# Busboard_v11.net
KiCad netlist of a schematic drawn in EAGLE
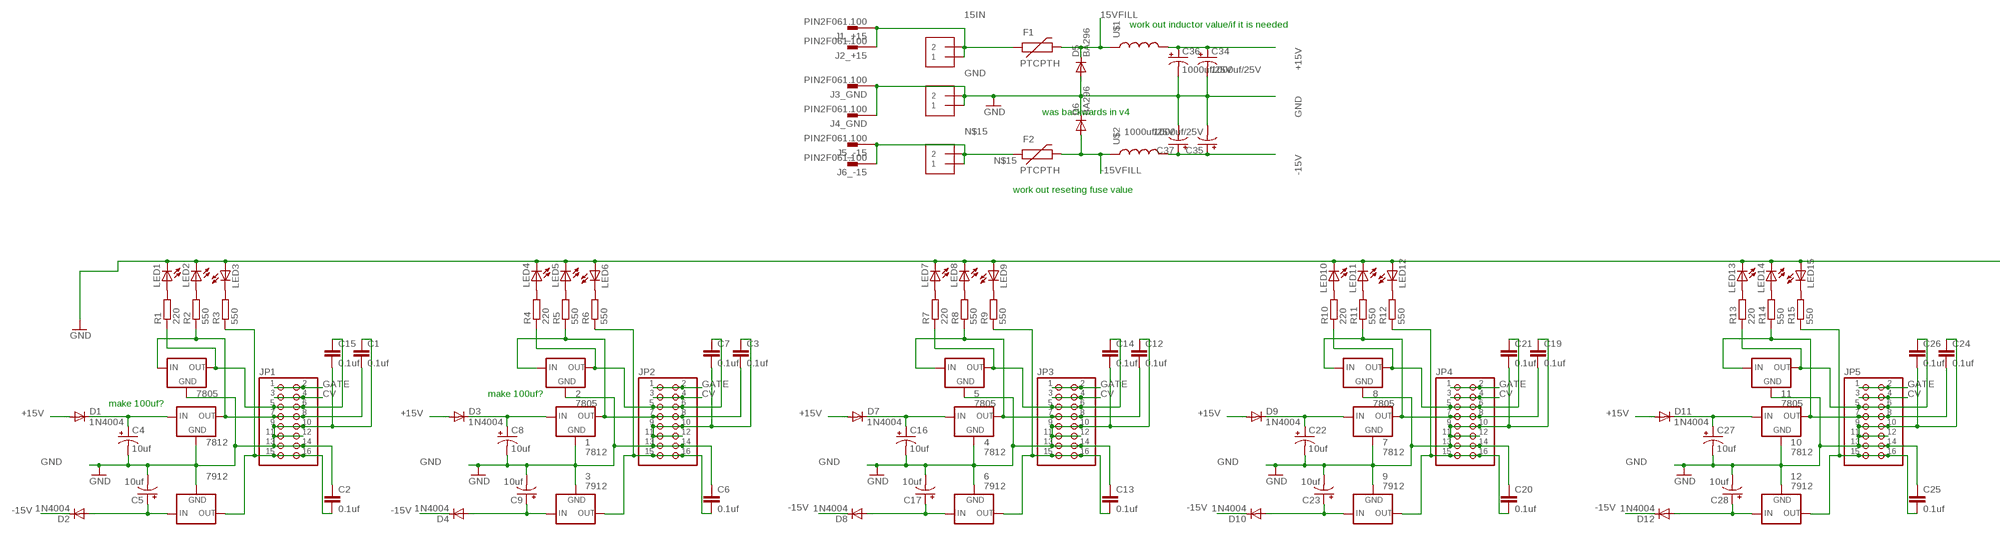
[diagram p0: schematic, sheet 1, part 1 of 2]
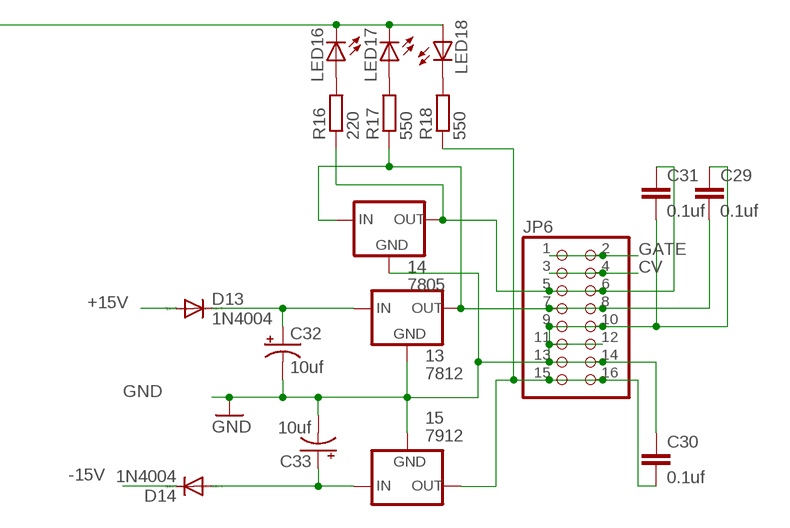
[diagram p1: schematic, sheet 1, part 2 of 2]

(export (version "E")
  (design (tool "Eeschema 10.0.6"))
  (components
    (comp (ref "+15V_DC_IN")
      (value "1X2-3.5MM")
      (footprint "eagle-import:1X2-3.5MM")
      (libsource (lib "eagle-import") (part "1X2-3.5MM"))
    )
    (comp (ref "-15V_DC_IN")
      (value "1X2-3.5MM")
      (footprint "eagle-import:1X2-3.5MM")
      (libsource (lib "eagle-import") (part "1X2-3.5MM"))
    )
    (comp (ref "1")
      (value "7812")
      (footprint "eagle-import:78MXXS")
      (libsource (lib "eagle-import") (part "78MXXS"))
    )
    (comp (ref "2")
      (value "7805")
      (footprint "eagle-import:78MXXS")
      (libsource (lib "eagle-import") (part "78MXXS"))
    )
    (comp (ref "3")
      (value "7912")
      (footprint "eagle-import:79XXS")
      (libsource (lib "eagle-import") (part "79XXS"))
    )
    (comp (ref "4")
      (value "7812")
      (footprint "eagle-import:78MXXS")
      (libsource (lib "eagle-import") (part "78MXXS"))
    )
    (comp (ref "5")
      (value "7805")
      (footprint "eagle-import:78MXXS")
      (libsource (lib "eagle-import") (part "78MXXS"))
    )
    (comp (ref "6")
      (value "7912")
      (footprint "eagle-import:79XXS")
      (libsource (lib "eagle-import") (part "79XXS"))
    )
    (comp (ref "7")
      (value "7812")
      (footprint "eagle-import:78MXXS")
      (libsource (lib "eagle-import") (part "78MXXS"))
    )
    (comp (ref "8")
      (value "7805")
      (footprint "eagle-import:78MXXS")
      (libsource (lib "eagle-import") (part "78MXXS"))
    )
    (comp (ref "9")
      (value "7912")
      (footprint "eagle-import:79XXS")
      (libsource (lib "eagle-import") (part "79XXS"))
    )
    (comp (ref "10")
      (value "7812")
      (footprint "eagle-import:78MXXS")
      (libsource (lib "eagle-import") (part "78MXXS"))
    )
    (comp (ref "11")
      (value "7805")
      (footprint "eagle-import:78MXXS")
      (libsource (lib "eagle-import") (part "78MXXS"))
    )
    (comp (ref "12")
      (value "7912")
      (footprint "eagle-import:79XXS")
      (libsource (lib "eagle-import") (part "79XXS"))
    )
    (comp (ref "13")
      (value "7812")
      (footprint "eagle-import:78MXXS")
      (libsource (lib "eagle-import") (part "78MXXS"))
    )
    (comp (ref "14")
      (value "7805")
      (footprint "eagle-import:78MXXS")
      (libsource (lib "eagle-import") (part "78MXXS"))
    )
    (comp (ref "15")
      (value "7912")
      (footprint "eagle-import:79XXS")
      (libsource (lib "eagle-import") (part "79XXS"))
    )
    (comp (ref "7805")
      (value "78MXXS")
      (footprint "eagle-import:78MXXS")
      (libsource (lib "eagle-import") (part "78MXXS"))
    )
    (comp (ref "7812")
      (value "78MXXS")
      (footprint "eagle-import:78MXXS")
      (libsource (lib "eagle-import") (part "78MXXS"))
    )
    (comp (ref "7912")
      (value "79XXS")
      (footprint "eagle-import:79XXS")
      (libsource (lib "eagle-import") (part "79XXS"))
    )
    (comp (ref "C1")
      (value "0.1uf")
      (footprint "eagle-import:CAP-PTH-SMALL-KIT")
      (libsource (lib "eagle-import") (part "0.1UF-50V-20%(PTH)KIT-EZ"))
    )
    (comp (ref "C2")
      (value "0.1uf")
      (footprint "eagle-import:CAP-PTH-SMALL-KIT")
      (libsource (lib "eagle-import") (part "0.1UF-50V-20%(PTH)KIT-EZ"))
    )
    (comp (ref "C3")
      (value "0.1uf")
      (footprint "eagle-import:CAP-PTH-SMALL-KIT")
      (libsource (lib "eagle-import") (part "0.1UF-50V-20%(PTH)KIT-EZ"))
    )
    (comp (ref "C4")
      (value "10uf")
      (footprint "eagle-import:CPOL-RADIAL-10UF-25V")
      (libsource (lib "eagle-import") (part "10UF-25V-20%(PTH)"))
    )
    (comp (ref "C5")
      (value "10uf")
      (footprint "eagle-import:CPOL-RADIAL-10UF-25V")
      (libsource (lib "eagle-import") (part "10UF-25V-20%(PTH)"))
    )
    (comp (ref "C6")
      (value "0.1uf")
      (footprint "eagle-import:CAP-PTH-SMALL-KIT")
      (libsource (lib "eagle-import") (part "0.1UF-50V-20%(PTH)KIT-EZ"))
    )
    (comp (ref "C7")
      (value "0.1uf")
      (footprint "eagle-import:CAP-PTH-SMALL-KIT")
      (libsource (lib "eagle-import") (part "0.1UF-50V-20%(PTH)KIT-EZ"))
    )
    (comp (ref "C8")
      (value "10uf")
      (footprint "eagle-import:CPOL-RADIAL-10UF-25V")
      (libsource (lib "eagle-import") (part "10UF-25V-20%(PTH)"))
    )
    (comp (ref "C9")
      (value "10uf")
      (footprint "eagle-import:CPOL-RADIAL-10UF-25V")
      (libsource (lib "eagle-import") (part "10UF-25V-20%(PTH)"))
    )
    (comp (ref "C12")
      (value "0.1uf")
      (footprint "eagle-import:CAP-PTH-SMALL-KIT")
      (libsource (lib "eagle-import") (part "0.1UF-50V-20%(PTH)KIT-EZ"))
    )
    (comp (ref "C13")
      (value "0.1uf")
      (footprint "eagle-import:CAP-PTH-SMALL-KIT")
      (libsource (lib "eagle-import") (part "0.1UF-50V-20%(PTH)KIT-EZ"))
    )
    (comp (ref "C14")
      (value "0.1uf")
      (footprint "eagle-import:CAP-PTH-SMALL-KIT")
      (libsource (lib "eagle-import") (part "0.1UF-50V-20%(PTH)KIT-EZ"))
    )
    (comp (ref "C15")
      (value "0.1uf")
      (footprint "eagle-import:CAP-PTH-SMALL-KIT")
      (libsource (lib "eagle-import") (part "0.1UF-50V-20%(PTH)KIT-EZ"))
    )
    (comp (ref "C16")
      (value "10uf")
      (footprint "eagle-import:CPOL-RADIAL-10UF-25V")
      (libsource (lib "eagle-import") (part "10UF-25V-20%(PTH)"))
    )
    (comp (ref "C17")
      (value "10uf")
      (footprint "eagle-import:CPOL-RADIAL-10UF-25V")
      (libsource (lib "eagle-import") (part "10UF-25V-20%(PTH)"))
    )
    (comp (ref "C19")
      (value "0.1uf")
      (footprint "eagle-import:CAP-PTH-SMALL-KIT")
      (libsource (lib "eagle-import") (part "0.1UF-50V-20%(PTH)KIT-EZ"))
    )
    (comp (ref "C20")
      (value "0.1uf")
      (footprint "eagle-import:CAP-PTH-SMALL-KIT")
      (libsource (lib "eagle-import") (part "0.1UF-50V-20%(PTH)KIT-EZ"))
    )
    (comp (ref "C21")
      (value "0.1uf")
      (footprint "eagle-import:CAP-PTH-SMALL-KIT")
      (libsource (lib "eagle-import") (part "0.1UF-50V-20%(PTH)KIT-EZ"))
    )
    (comp (ref "C22")
      (value "10uf")
      (footprint "eagle-import:CPOL-RADIAL-10UF-25V")
      (libsource (lib "eagle-import") (part "10UF-25V-20%(PTH)"))
    )
    (comp (ref "C23")
      (value "10uf")
      (footprint "eagle-import:CPOL-RADIAL-10UF-25V")
      (libsource (lib "eagle-import") (part "10UF-25V-20%(PTH)"))
    )
    (comp (ref "C24")
      (value "0.1uf")
      (footprint "eagle-import:CAP-PTH-SMALL-KIT")
      (libsource (lib "eagle-import") (part "0.1UF-50V-20%(PTH)KIT-EZ"))
    )
    (comp (ref "C25")
      (value "0.1uf")
      (footprint "eagle-import:CAP-PTH-SMALL-KIT")
      (libsource (lib "eagle-import") (part "0.1UF-50V-20%(PTH)KIT-EZ"))
    )
    (comp (ref "C26")
      (value "0.1uf")
      (footprint "eagle-import:CAP-PTH-SMALL-KIT")
      (libsource (lib "eagle-import") (part "0.1UF-50V-20%(PTH)KIT-EZ"))
    )
    (comp (ref "C27")
      (value "10uf")
      (footprint "eagle-import:CPOL-RADIAL-10UF-25V")
      (libsource (lib "eagle-import") (part "10UF-25V-20%(PTH)"))
    )
    (comp (ref "C28")
      (value "10uf")
      (footprint "eagle-import:CPOL-RADIAL-10UF-25V")
      (libsource (lib "eagle-import") (part "10UF-25V-20%(PTH)"))
    )
    (comp (ref "C29")
      (value "0.1uf")
      (footprint "eagle-import:CAP-PTH-SMALL-KIT")
      (libsource (lib "eagle-import") (part "0.1UF-50V-20%(PTH)KIT-EZ"))
    )
    (comp (ref "C30")
      (value "0.1uf")
      (footprint "eagle-import:CAP-PTH-SMALL-KIT")
      (libsource (lib "eagle-import") (part "0.1UF-50V-20%(PTH)KIT-EZ"))
    )
    (comp (ref "C31")
      (value "0.1uf")
      (footprint "eagle-import:CAP-PTH-SMALL-KIT")
      (libsource (lib "eagle-import") (part "0.1UF-50V-20%(PTH)KIT-EZ"))
    )
    (comp (ref "C32")
      (value "10uf")
      (footprint "eagle-import:CPOL-RADIAL-10UF-25V")
      (libsource (lib "eagle-import") (part "10UF-25V-20%(PTH)"))
    )
    (comp (ref "C33")
      (value "10uf")
      (footprint "eagle-import:CPOL-RADIAL-10UF-25V")
      (libsource (lib "eagle-import") (part "10UF-25V-20%(PTH)"))
    )
    (comp (ref "C34")
      (value "1000uf/25V")
      (footprint "eagle-import:CPOL-RADIAL-1000UF-25V-KIT")
      (libsource (lib "eagle-import") (part "1000UF-25V(PTH)KIT"))
    )
    (comp (ref "C35")
      (value "1000uf/25V")
      (footprint "eagle-import:CPOL-RADIAL-1000UF-25V-KIT")
      (libsource (lib "eagle-import") (part "1000UF-25V(PTH)KIT"))
    )
    (comp (ref "C36")
      (value "1000uf/25V")
      (footprint "eagle-import:CPOL-RADIAL-1000UF-25V-KIT")
      (libsource (lib "eagle-import") (part "1000UF-25V(PTH)KIT"))
    )
    (comp (ref "C37")
      (value "1000uf/25V")
      (footprint "eagle-import:CPOL-RADIAL-1000UF-25V-KIT")
      (libsource (lib "eagle-import") (part "1000UF-25V(PTH)KIT"))
    )
    (comp (ref "D1")
      (value "1N4004")
      (footprint "eagle-import:DO41-10")
      (libsource (lib "eagle-import") (part "1N4004"))
    )
    (comp (ref "D2")
      (value "1N4004")
      (footprint "eagle-import:DO41-10")
      (libsource (lib "eagle-import") (part "1N4004"))
    )
    (comp (ref "D3")
      (value "1N4004")
      (footprint "eagle-import:DO41-10")
      (libsource (lib "eagle-import") (part "1N4004"))
    )
    (comp (ref "D4")
      (value "1N4004")
      (footprint "eagle-import:DO41-10")
      (libsource (lib "eagle-import") (part "1N4004"))
    )
    (comp (ref "D5")
      (value "BA296")
      (footprint "eagle-import:P2-15")
      (libsource (lib "eagle-import") (part "BA296"))
    )
    (comp (ref "D6")
      (value "BA296")
      (footprint "eagle-import:P2-15")
      (libsource (lib "eagle-import") (part "BA296"))
    )
    (comp (ref "D7")
      (value "1N4004")
      (footprint "eagle-import:DO41-10")
      (libsource (lib "eagle-import") (part "1N4004"))
    )
    (comp (ref "D8")
      (value "1N4004")
      (footprint "eagle-import:DO41-10")
      (libsource (lib "eagle-import") (part "1N4004"))
    )
    (comp (ref "D9")
      (value "1N4004")
      (footprint "eagle-import:DO41-10")
      (libsource (lib "eagle-import") (part "1N4004"))
    )
    (comp (ref "D10")
      (value "1N4004")
      (footprint "eagle-import:DO41-10")
      (libsource (lib "eagle-import") (part "1N4004"))
    )
    (comp (ref "D11")
      (value "1N4004")
      (footprint "eagle-import:DO41-10")
      (libsource (lib "eagle-import") (part "1N4004"))
    )
    (comp (ref "D12")
      (value "1N4004")
      (footprint "eagle-import:DO41-10")
      (libsource (lib "eagle-import") (part "1N4004"))
    )
    (comp (ref "D13")
      (value "1N4004")
      (footprint "eagle-import:DO41-10")
      (libsource (lib "eagle-import") (part "1N4004"))
    )
    (comp (ref "D14")
      (value "1N4004")
      (footprint "eagle-import:DO41-10")
      (libsource (lib "eagle-import") (part "1N4004"))
    )
    (comp (ref "F1")
      (value "PTCPTH")
      (footprint "eagle-import:PTC")
      (libsource (lib "eagle-import") (part "PTCPTH"))
    )
    (comp (ref "F2")
      (value "PTCPTH")
      (footprint "eagle-import:PTC")
      (libsource (lib "eagle-import") (part "PTCPTH"))
    )
    (comp (ref "GND_IN")
      (value "1X2-3.5MM")
      (footprint "eagle-import:1X2-3.5MM")
      (libsource (lib "eagle-import") (part "1X2-3.5MM"))
    )
    (comp (ref "J1_+15")
      (value "PIN2F061.100")
      (footprint "eagle-import:F061.100")
      (libsource (lib "eagle-import") (part "PIN2F061.100"))
    )
    (comp (ref "J2_+15")
      (value "PIN2F061.100")
      (footprint "eagle-import:F061.100")
      (libsource (lib "eagle-import") (part "PIN2F061.100"))
    )
    (comp (ref "J3_GND")
      (value "PIN2F061.100")
      (footprint "eagle-import:F061.100")
      (libsource (lib "eagle-import") (part "PIN2F061.100"))
    )
    (comp (ref "J4_GND")
      (value "PIN2F061.100")
      (footprint "eagle-import:F061.100")
      (libsource (lib "eagle-import") (part "PIN2F061.100"))
    )
    (comp (ref "J5_-15")
      (value "PIN2F061.100")
      (footprint "eagle-import:F061.100")
      (libsource (lib "eagle-import") (part "PIN2F061.100"))
    )
    (comp (ref "J6_-15")
      (value "PIN2F061.100")
      (footprint "eagle-import:F061.100")
      (libsource (lib "eagle-import") (part "PIN2F061.100"))
    )
    (comp (ref "JP1")
      (value "PINHD-2X8")
      (footprint "eagle-import:2X08")
      (libsource (lib "eagle-import") (part "PINHD-2X8"))
    )
    (comp (ref "JP2")
      (value "PINHD-2X8")
      (footprint "eagle-import:2X08")
      (libsource (lib "eagle-import") (part "PINHD-2X8"))
    )
    (comp (ref "JP3")
      (value "PINHD-2X8")
      (footprint "eagle-import:2X08")
      (libsource (lib "eagle-import") (part "PINHD-2X8"))
    )
    (comp (ref "JP4")
      (value "PINHD-2X8")
      (footprint "eagle-import:2X08")
      (libsource (lib "eagle-import") (part "PINHD-2X8"))
    )
    (comp (ref "JP5")
      (value "PINHD-2X8")
      (footprint "eagle-import:2X08")
      (libsource (lib "eagle-import") (part "PINHD-2X8"))
    )
    (comp (ref "JP6")
      (value "PINHD-2X8")
      (footprint "eagle-import:2X08")
      (libsource (lib "eagle-import") (part "PINHD-2X8"))
    )
    (comp (ref "LED1")
      (value "LED3MM")
      (footprint "eagle-import:LED3MM")
      (libsource (lib "eagle-import") (part "LED3MM"))
    )
    (comp (ref "LED2")
      (value "LED3MM")
      (footprint "eagle-import:LED3MM")
      (libsource (lib "eagle-import") (part "LED3MM"))
    )
    (comp (ref "LED3")
      (value "LED3MM")
      (footprint "eagle-import:LED3MM")
      (libsource (lib "eagle-import") (part "LED3MM"))
    )
    (comp (ref "LED4")
      (value "LED3MM")
      (footprint "eagle-import:LED3MM")
      (libsource (lib "eagle-import") (part "LED3MM"))
    )
    (comp (ref "LED5")
      (value "LED3MM")
      (footprint "eagle-import:LED3MM")
      (libsource (lib "eagle-import") (part "LED3MM"))
    )
    (comp (ref "LED6")
      (value "LED3MM")
      (footprint "eagle-import:LED3MM")
      (libsource (lib "eagle-import") (part "LED3MM"))
    )
    (comp (ref "LED7")
      (value "LED3MM")
      (footprint "eagle-import:LED3MM")
      (libsource (lib "eagle-import") (part "LED3MM"))
    )
    (comp (ref "LED8")
      (value "LED3MM")
      (footprint "eagle-import:LED3MM")
      (libsource (lib "eagle-import") (part "LED3MM"))
    )
    (comp (ref "LED9")
      (value "LED3MM")
      (footprint "eagle-import:LED3MM")
      (libsource (lib "eagle-import") (part "LED3MM"))
    )
    (comp (ref "LED10")
      (value "LED3MM")
      (footprint "eagle-import:LED3MM")
      (libsource (lib "eagle-import") (part "LED3MM"))
    )
    (comp (ref "LED11")
      (value "LED3MM")
      (footprint "eagle-import:LED3MM")
      (libsource (lib "eagle-import") (part "LED3MM"))
    )
    (comp (ref "LED12")
      (value "LED3MM")
      (footprint "eagle-import:LED3MM")
      (libsource (lib "eagle-import") (part "LED3MM"))
    )
    (comp (ref "LED13")
      (value "LED3MM")
      (footprint "eagle-import:LED3MM")
      (libsource (lib "eagle-import") (part "LED3MM"))
    )
    (comp (ref "LED14")
      (value "LED3MM")
      (footprint "eagle-import:LED3MM")
      (libsource (lib "eagle-import") (part "LED3MM"))
    )
    (comp (ref "LED15")
      (value "LED3MM")
      (footprint "eagle-import:LED3MM")
      (libsource (lib "eagle-import") (part "LED3MM"))
    )
    (comp (ref "LED16")
      (value "LED3MM")
      (footprint "eagle-import:LED3MM")
      (libsource (lib "eagle-import") (part "LED3MM"))
    )
    (comp (ref "LED17")
      (value "LED3MM")
      (footprint "eagle-import:LED3MM")
      (libsource (lib "eagle-import") (part "LED3MM"))
    )
    (comp (ref "LED18")
      (value "LED3MM")
      (footprint "eagle-import:LED3MM")
      (libsource (lib "eagle-import") (part "LED3MM"))
    )
    (comp (ref "R1")
      (value "220")
      (footprint "eagle-import:0207_5V")
      (libsource (lib "eagle-import") (part "R-EU_0207/5V"))
    )
    (comp (ref "R2")
      (value "550")
      (footprint "eagle-import:0207_5V")
      (libsource (lib "eagle-import") (part "R-EU_0207/5V"))
    )
    (comp (ref "R3")
      (value "550")
      (footprint "eagle-import:0207_5V")
      (libsource (lib "eagle-import") (part "R-EU_0207/5V"))
    )
    (comp (ref "R4")
      (value "220")
      (footprint "eagle-import:0207_5V")
      (libsource (lib "eagle-import") (part "R-EU_0207/5V"))
    )
    (comp (ref "R5")
      (value "550")
      (footprint "eagle-import:0207_5V")
      (libsource (lib "eagle-import") (part "R-EU_0207/5V"))
    )
    (comp (ref "R6")
      (value "550")
      (footprint "eagle-import:0207_5V")
      (libsource (lib "eagle-import") (part "R-EU_0207/5V"))
    )
    (comp (ref "R7")
      (value "220")
      (footprint "eagle-import:0207_5V")
      (libsource (lib "eagle-import") (part "R-EU_0207/5V"))
    )
    (comp (ref "R8")
      (value "550")
      (footprint "eagle-import:0207_5V")
      (libsource (lib "eagle-import") (part "R-EU_0207/5V"))
    )
    (comp (ref "R9")
      (value "550")
      (footprint "eagle-import:0207_5V")
      (libsource (lib "eagle-import") (part "R-EU_0207/5V"))
    )
    (comp (ref "R10")
      (value "220")
      (footprint "eagle-import:0207_5V")
      (libsource (lib "eagle-import") (part "R-EU_0207/5V"))
    )
    (comp (ref "R11")
      (value "550")
      (footprint "eagle-import:0207_5V")
      (libsource (lib "eagle-import") (part "R-EU_0207/5V"))
    )
    (comp (ref "R12")
      (value "550")
      (footprint "eagle-import:0207_5V")
      (libsource (lib "eagle-import") (part "R-EU_0207/5V"))
    )
    (comp (ref "R13")
      (value "220")
      (footprint "eagle-import:0207_5V")
      (libsource (lib "eagle-import") (part "R-EU_0207/5V"))
    )
    (comp (ref "R14")
      (value "550")
      (footprint "eagle-import:0207_5V")
      (libsource (lib "eagle-import") (part "R-EU_0207/5V"))
    )
    (comp (ref "R15")
      (value "550")
      (footprint "eagle-import:0207_5V")
      (libsource (lib "eagle-import") (part "R-EU_0207/5V"))
    )
    (comp (ref "R16")
      (value "220")
      (footprint "eagle-import:0207_5V")
      (libsource (lib "eagle-import") (part "R-EU_0207/5V"))
    )
    (comp (ref "R17")
      (value "550")
      (footprint "eagle-import:0207_5V")
      (libsource (lib "eagle-import") (part "R-EU_0207/5V"))
    )
    (comp (ref "R18")
      (value "550")
      (footprint "eagle-import:0207_5V")
      (libsource (lib "eagle-import") (part "R-EU_0207/5V"))
    )
    (comp (ref "U$1")
      (value "INDUCTORRLB0912")
      (footprint "eagle-import:RLB0912")
      (libsource (lib "eagle-import") (part "INDUCTORRLB0912"))
    )
    (comp (ref "U$2")
      (value "INDUCTORRLB0912")
      (footprint "eagle-import:RLB0912")
      (libsource (lib "eagle-import") (part "INDUCTORRLB0912"))
    )
  )
  (nets
    (net (code "1") (name "/+15V") (class "Default")
      (node (ref "C34") (pin "+") (pinfunction "+_+") (pintype "passive"))
      (node (ref "C36") (pin "+") (pinfunction "+_+") (pintype "passive"))
      (node (ref "D1") (pin "A") (pinfunction "A_A") (pintype "passive"))
      (node (ref "D11") (pin "A") (pinfunction "A_A") (pintype "passive"))
      (node (ref "D13") (pin "A") (pinfunction "A_A") (pintype "passive"))
      (node (ref "D3") (pin "A") (pinfunction "A_A") (pintype "passive"))
      (node (ref "D7") (pin "A") (pinfunction "A_A") (pintype "passive"))
      (node (ref "D9") (pin "A") (pinfunction "A_A") (pintype "passive"))
      (node (ref "U$1") (pin "2") (pinfunction "2_2") (pintype "passive"))
    )
    (net (code "2") (name "/-15V") (class "Default")
      (node (ref "C35") (pin "+") (pinfunction "+_+") (pintype "passive"))
      (node (ref "C37") (pin "+") (pinfunction "+_+") (pintype "passive"))
      (node (ref "D10") (pin "C") (pinfunction "C_C") (pintype "passive"))
      (node (ref "D12") (pin "C") (pinfunction "C_C") (pintype "passive"))
      (node (ref "D14") (pin "C") (pinfunction "C_C") (pintype "passive"))
      (node (ref "D2") (pin "C") (pinfunction "C_C") (pintype "passive"))
      (node (ref "D4") (pin "C") (pinfunction "C_C") (pintype "passive"))
      (node (ref "D8") (pin "C") (pinfunction "C_C") (pintype "passive"))
      (node (ref "U$2") (pin "2") (pinfunction "2_2") (pintype "passive"))
    )
    (net (code "3") (name "/-15VFILL") (class "Default")
      (node (ref "D6") (pin "A") (pinfunction "A_A") (pintype "passive"))
      (node (ref "F2") (pin "P$2") (pinfunction "2_P$2") (pintype "bidirectional"))
      (node (ref "U$2") (pin "1") (pinfunction "1_1") (pintype "passive"))
    )
    (net (code "4") (name "/15IN") (class "Default")
      (node (ref "+15V_DC_IN") (pin "1") (pinfunction "1_1") (pintype "passive"))
      (node (ref "+15V_DC_IN") (pin "2") (pinfunction "2_2") (pintype "passive"))
      (node (ref "F1") (pin "P$1") (pinfunction "1_P$1") (pintype "bidirectional"))
      (node (ref "J1_+15") (pin "A1") (pinfunction "1_A1") (pintype "passive"))
      (node (ref "J1_+15") (pin "A2") (pinfunction "1_A2") (pintype "passive"))
      (node (ref "J2_+15") (pin "A1") (pinfunction "1_A1") (pintype "passive"))
      (node (ref "J2_+15") (pin "A2") (pinfunction "1_A2") (pintype "passive"))
    )
    (net (code "5") (name "/15VFILL") (class "Default")
      (node (ref "D5") (pin "C") (pinfunction "C_C") (pintype "passive"))
      (node (ref "F1") (pin "P$2") (pinfunction "2_P$2") (pintype "bidirectional"))
      (node (ref "U$1") (pin "1") (pinfunction "1_1") (pintype "passive"))
    )
    (net (code "6") (name "/CV") (class "Default")
      (node (ref "JP1") (pin "3") (pinfunction "3_3") (pintype "passive"))
      (node (ref "JP1") (pin "4") (pinfunction "4_4") (pintype "passive"))
      (node (ref "JP2") (pin "3") (pinfunction "3_3") (pintype "passive"))
      (node (ref "JP2") (pin "4") (pinfunction "4_4") (pintype "passive"))
      (node (ref "JP3") (pin "3") (pinfunction "3_3") (pintype "passive"))
      (node (ref "JP3") (pin "4") (pinfunction "4_4") (pintype "passive"))
      (node (ref "JP4") (pin "3") (pinfunction "3_3") (pintype "passive"))
      (node (ref "JP4") (pin "4") (pinfunction "4_4") (pintype "passive"))
      (node (ref "JP5") (pin "3") (pinfunction "3_3") (pintype "passive"))
      (node (ref "JP5") (pin "4") (pinfunction "4_4") (pintype "passive"))
      (node (ref "JP6") (pin "3") (pinfunction "3_3") (pintype "passive"))
      (node (ref "JP6") (pin "4") (pinfunction "4_4") (pintype "passive"))
    )
    (net (code "7") (name "/GATE") (class "Default")
      (node (ref "JP1") (pin "1") (pinfunction "1_1") (pintype "passive"))
      (node (ref "JP1") (pin "2") (pinfunction "2_2") (pintype "passive"))
      (node (ref "JP2") (pin "1") (pinfunction "1_1") (pintype "passive"))
      (node (ref "JP2") (pin "2") (pinfunction "2_2") (pintype "passive"))
      (node (ref "JP3") (pin "1") (pinfunction "1_1") (pintype "passive"))
      (node (ref "JP3") (pin "2") (pinfunction "2_2") (pintype "passive"))
      (node (ref "JP4") (pin "1") (pinfunction "1_1") (pintype "passive"))
      (node (ref "JP4") (pin "2") (pinfunction "2_2") (pintype "passive"))
      (node (ref "JP5") (pin "1") (pinfunction "1_1") (pintype "passive"))
      (node (ref "JP5") (pin "2") (pinfunction "2_2") (pintype "passive"))
      (node (ref "JP6") (pin "1") (pinfunction "1_1") (pintype "passive"))
      (node (ref "JP6") (pin "2") (pinfunction "2_2") (pintype "passive"))
    )
    (net (code "8") (name "/N$15") (class "Default")
      (node (ref "-15V_DC_IN") (pin "1") (pinfunction "1_1") (pintype "passive"))
      (node (ref "-15V_DC_IN") (pin "2") (pinfunction "2_2") (pintype "passive"))
      (node (ref "F2") (pin "P$1") (pinfunction "1_P$1") (pintype "bidirectional"))
      (node (ref "J5_-15") (pin "A1") (pinfunction "1_A1") (pintype "passive"))
      (node (ref "J5_-15") (pin "A2") (pinfunction "1_A2") (pintype "passive"))
      (node (ref "J6_-15") (pin "A1") (pinfunction "1_A1") (pintype "passive"))
      (node (ref "J6_-15") (pin "A2") (pinfunction "1_A2") (pintype "passive"))
    )
    (net (code "9") (name "GND") (class "Default")
      (node (ref "1") (pin "GND") (pinfunction "GND_GND") (pintype "input"))
      (node (ref "10") (pin "GND") (pinfunction "GND_GND") (pintype "input"))
      (node (ref "11") (pin "GND") (pinfunction "GND_GND") (pintype "input"))
      (node (ref "12") (pin "GND") (pinfunction "GND_GND") (pintype "input"))
      (node (ref "13") (pin "GND") (pinfunction "GND_GND") (pintype "input"))
      (node (ref "14") (pin "GND") (pinfunction "GND_GND") (pintype "input"))
      (node (ref "15") (pin "GND") (pinfunction "GND_GND") (pintype "input"))
      (node (ref "2") (pin "GND") (pinfunction "GND_GND") (pintype "input"))
      (node (ref "3") (pin "GND") (pinfunction "GND_GND") (pintype "input"))
      (node (ref "4") (pin "GND") (pinfunction "GND_GND") (pintype "input"))
      (node (ref "5") (pin "GND") (pinfunction "GND_GND") (pintype "input"))
      (node (ref "6") (pin "GND") (pinfunction "GND_GND") (pintype "input"))
      (node (ref "7") (pin "GND") (pinfunction "GND_GND") (pintype "input"))
      (node (ref "7805") (pin "GND") (pinfunction "GND_GND") (pintype "input"))
      (node (ref "7812") (pin "GND") (pinfunction "GND_GND") (pintype "input"))
      (node (ref "7912") (pin "GND") (pinfunction "GND_GND") (pintype "input"))
      (node (ref "8") (pin "GND") (pinfunction "GND_GND") (pintype "input"))
      (node (ref "9") (pin "GND") (pinfunction "GND_GND") (pintype "input"))
      (node (ref "C1") (pin "1") (pinfunction "1_1") (pintype "passive"))
      (node (ref "C12") (pin "1") (pinfunction "1_1") (pintype "passive"))
      (node (ref "C13") (pin "1") (pinfunction "1_1") (pintype "passive"))
      (node (ref "C14") (pin "2") (pinfunction "2_2") (pintype "passive"))
      (node (ref "C15") (pin "2") (pinfunction "2_2") (pintype "passive"))
      (node (ref "C16") (pin "2") (pinfunction "-_2") (pintype "passive"))
      (node (ref "C17") (pin "2") (pinfunction "-_2") (pintype "passive"))
      (node (ref "C19") (pin "1") (pinfunction "1_1") (pintype "passive"))
      (node (ref "C2") (pin "1") (pinfunction "1_1") (pintype "passive"))
      (node (ref "C20") (pin "1") (pinfunction "1_1") (pintype "passive"))
      (node (ref "C21") (pin "2") (pinfunction "2_2") (pintype "passive"))
      (node (ref "C22") (pin "2") (pinfunction "-_2") (pintype "passive"))
      (node (ref "C23") (pin "2") (pinfunction "-_2") (pintype "passive"))
      (node (ref "C24") (pin "1") (pinfunction "1_1") (pintype "passive"))
      (node (ref "C25") (pin "1") (pinfunction "1_1") (pintype "passive"))
      (node (ref "C26") (pin "2") (pinfunction "2_2") (pintype "passive"))
      (node (ref "C27") (pin "2") (pinfunction "-_2") (pintype "passive"))
      (node (ref "C28") (pin "2") (pinfunction "-_2") (pintype "passive"))
      (node (ref "C29") (pin "1") (pinfunction "1_1") (pintype "passive"))
      (node (ref "C3") (pin "1") (pinfunction "1_1") (pintype "passive"))
      (node (ref "C30") (pin "1") (pinfunction "1_1") (pintype "passive"))
      (node (ref "C31") (pin "2") (pinfunction "2_2") (pintype "passive"))
      (node (ref "C32") (pin "2") (pinfunction "-_2") (pintype "passive"))
      (node (ref "C33") (pin "2") (pinfunction "-_2") (pintype "passive"))
      (node (ref "C34") (pin "-") (pinfunction "-_-") (pintype "passive"))
      (node (ref "C35") (pin "-") (pinfunction "-_-") (pintype "passive"))
      (node (ref "C36") (pin "-") (pinfunction "-_-") (pintype "passive"))
      (node (ref "C37") (pin "-") (pinfunction "-_-") (pintype "passive"))
      (node (ref "C4") (pin "2") (pinfunction "-_2") (pintype "passive"))
      (node (ref "C5") (pin "2") (pinfunction "-_2") (pintype "passive"))
      (node (ref "C6") (pin "1") (pinfunction "1_1") (pintype "passive"))
      (node (ref "C7") (pin "2") (pinfunction "2_2") (pintype "passive"))
      (node (ref "C8") (pin "2") (pinfunction "-_2") (pintype "passive"))
      (node (ref "C9") (pin "2") (pinfunction "-_2") (pintype "passive"))
      (node (ref "D5") (pin "A") (pinfunction "A_A") (pintype "passive"))
      (node (ref "D6") (pin "C") (pinfunction "C_C") (pintype "passive"))
      (node (ref "GND_IN") (pin "1") (pinfunction "1_1") (pintype "passive"))
      (node (ref "GND_IN") (pin "2") (pinfunction "2_2") (pintype "passive"))
      (node (ref "J3_GND") (pin "A1") (pinfunction "1_A1") (pintype "passive"))
      (node (ref "J3_GND") (pin "A2") (pinfunction "1_A2") (pintype "passive"))
      (node (ref "J4_GND") (pin "A1") (pinfunction "1_A1") (pintype "passive"))
      (node (ref "J4_GND") (pin "A2") (pinfunction "1_A2") (pintype "passive"))
      (node (ref "JP1") (pin "10") (pinfunction "10_10") (pintype "passive"))
      (node (ref "JP1") (pin "11") (pinfunction "11_11") (pintype "passive"))
      (node (ref "JP1") (pin "12") (pinfunction "12_12") (pintype "passive"))
      (node (ref "JP1") (pin "13") (pinfunction "13_13") (pintype "passive"))
      (node (ref "JP1") (pin "14") (pinfunction "14_14") (pintype "passive"))
      (node (ref "JP1") (pin "9") (pinfunction "9_9") (pintype "passive"))
      (node (ref "JP2") (pin "10") (pinfunction "10_10") (pintype "passive"))
      (node (ref "JP2") (pin "11") (pinfunction "11_11") (pintype "passive"))
      (node (ref "JP2") (pin "12") (pinfunction "12_12") (pintype "passive"))
      (node (ref "JP2") (pin "13") (pinfunction "13_13") (pintype "passive"))
      (node (ref "JP2") (pin "14") (pinfunction "14_14") (pintype "passive"))
      (node (ref "JP2") (pin "9") (pinfunction "9_9") (pintype "passive"))
      (node (ref "JP3") (pin "10") (pinfunction "10_10") (pintype "passive"))
      (node (ref "JP3") (pin "11") (pinfunction "11_11") (pintype "passive"))
      (node (ref "JP3") (pin "12") (pinfunction "12_12") (pintype "passive"))
      (node (ref "JP3") (pin "13") (pinfunction "13_13") (pintype "passive"))
      (node (ref "JP3") (pin "14") (pinfunction "14_14") (pintype "passive"))
      (node (ref "JP3") (pin "9") (pinfunction "9_9") (pintype "passive"))
      (node (ref "JP4") (pin "10") (pinfunction "10_10") (pintype "passive"))
      (node (ref "JP4") (pin "11") (pinfunction "11_11") (pintype "passive"))
      (node (ref "JP4") (pin "12") (pinfunction "12_12") (pintype "passive"))
      (node (ref "JP4") (pin "13") (pinfunction "13_13") (pintype "passive"))
      (node (ref "JP4") (pin "14") (pinfunction "14_14") (pintype "passive"))
      (node (ref "JP4") (pin "9") (pinfunction "9_9") (pintype "passive"))
      (node (ref "JP5") (pin "10") (pinfunction "10_10") (pintype "passive"))
      (node (ref "JP5") (pin "11") (pinfunction "11_11") (pintype "passive"))
      (node (ref "JP5") (pin "12") (pinfunction "12_12") (pintype "passive"))
      (node (ref "JP5") (pin "13") (pinfunction "13_13") (pintype "passive"))
      (node (ref "JP5") (pin "14") (pinfunction "14_14") (pintype "passive"))
      (node (ref "JP5") (pin "9") (pinfunction "9_9") (pintype "passive"))
      (node (ref "JP6") (pin "10") (pinfunction "10_10") (pintype "passive"))
      (node (ref "JP6") (pin "11") (pinfunction "11_11") (pintype "passive"))
      (node (ref "JP6") (pin "12") (pinfunction "12_12") (pintype "passive"))
      (node (ref "JP6") (pin "13") (pinfunction "13_13") (pintype "passive"))
      (node (ref "JP6") (pin "14") (pinfunction "14_14") (pintype "passive"))
      (node (ref "JP6") (pin "9") (pinfunction "9_9") (pintype "passive"))
      (node (ref "LED1") (pin "K") (pinfunction "C_K") (pintype "passive"))
      (node (ref "LED10") (pin "K") (pinfunction "C_K") (pintype "passive"))
      (node (ref "LED11") (pin "K") (pinfunction "C_K") (pintype "passive"))
      (node (ref "LED12") (pin "A") (pinfunction "A_A") (pintype "passive"))
      (node (ref "LED13") (pin "K") (pinfunction "C_K") (pintype "passive"))
      (node (ref "LED14") (pin "K") (pinfunction "C_K") (pintype "passive"))
      (node (ref "LED15") (pin "A") (pinfunction "A_A") (pintype "passive"))
      (node (ref "LED16") (pin "K") (pinfunction "C_K") (pintype "passive"))
      (node (ref "LED17") (pin "K") (pinfunction "C_K") (pintype "passive"))
      (node (ref "LED18") (pin "A") (pinfunction "A_A") (pintype "passive"))
      (node (ref "LED2") (pin "K") (pinfunction "C_K") (pintype "passive"))
      (node (ref "LED3") (pin "A") (pinfunction "A_A") (pintype "passive"))
      (node (ref "LED4") (pin "K") (pinfunction "C_K") (pintype "passive"))
      (node (ref "LED5") (pin "K") (pinfunction "C_K") (pintype "passive"))
      (node (ref "LED6") (pin "A") (pinfunction "A_A") (pintype "passive"))
      (node (ref "LED7") (pin "K") (pinfunction "C_K") (pintype "passive"))
      (node (ref "LED8") (pin "K") (pinfunction "C_K") (pintype "passive"))
      (node (ref "LED9") (pin "A") (pinfunction "A_A") (pintype "passive"))
    )
    (net (code "10") (name "Net-(1-PadOUT)") (class "Default")
      (node (ref "1") (pin "OUT") (pinfunction "OUT_OUT") (pintype "passive"))
      (node (ref "2") (pin "IN") (pinfunction "IN_IN") (pintype "input"))
      (node (ref "C3") (pin "2") (pinfunction "2_2") (pintype "passive"))
      (node (ref "JP2") (pin "7") (pinfunction "7_7") (pintype "passive"))
      (node (ref "JP2") (pin "8") (pinfunction "8_8") (pintype "passive"))
      (node (ref "R5") (pin "1") (pinfunction "1_1") (pintype "passive"))
    )
    (net (code "11") (name "Net-(2-PadOUT)") (class "Default")
      (node (ref "2") (pin "OUT") (pinfunction "OUT_OUT") (pintype "passive"))
      (node (ref "C7") (pin "1") (pinfunction "1_1") (pintype "passive"))
      (node (ref "JP2") (pin "5") (pinfunction "5_5") (pintype "passive"))
      (node (ref "JP2") (pin "6") (pinfunction "6_6") (pintype "passive"))
      (node (ref "R4") (pin "1") (pinfunction "1_1") (pintype "passive"))
    )
    (net (code "12") (name "Net-(3-PadOUT)") (class "Default")
      (node (ref "3") (pin "OUT") (pinfunction "OUT_OUT") (pintype "passive"))
      (node (ref "C6") (pin "2") (pinfunction "2_2") (pintype "passive"))
      (node (ref "JP2") (pin "15") (pinfunction "15_15") (pintype "passive"))
      (node (ref "JP2") (pin "16") (pinfunction "16_16") (pintype "passive"))
      (node (ref "R6") (pin "1") (pinfunction "1_1") (pintype "passive"))
    )
    (net (code "13") (name "Net-(4-PadOUT)") (class "Default")
      (node (ref "4") (pin "OUT") (pinfunction "OUT_OUT") (pintype "passive"))
      (node (ref "5") (pin "IN") (pinfunction "IN_IN") (pintype "input"))
      (node (ref "C12") (pin "2") (pinfunction "2_2") (pintype "passive"))
      (node (ref "JP3") (pin "7") (pinfunction "7_7") (pintype "passive"))
      (node (ref "JP3") (pin "8") (pinfunction "8_8") (pintype "passive"))
      (node (ref "R8") (pin "1") (pinfunction "1_1") (pintype "passive"))
    )
    (net (code "14") (name "Net-(5-PadOUT)") (class "Default")
      (node (ref "5") (pin "OUT") (pinfunction "OUT_OUT") (pintype "passive"))
      (node (ref "C14") (pin "1") (pinfunction "1_1") (pintype "passive"))
      (node (ref "JP3") (pin "5") (pinfunction "5_5") (pintype "passive"))
      (node (ref "JP3") (pin "6") (pinfunction "6_6") (pintype "passive"))
      (node (ref "R7") (pin "1") (pinfunction "1_1") (pintype "passive"))
    )
    (net (code "15") (name "Net-(6-PadOUT)") (class "Default")
      (node (ref "6") (pin "OUT") (pinfunction "OUT_OUT") (pintype "passive"))
      (node (ref "C13") (pin "2") (pinfunction "2_2") (pintype "passive"))
      (node (ref "JP3") (pin "15") (pinfunction "15_15") (pintype "passive"))
      (node (ref "JP3") (pin "16") (pinfunction "16_16") (pintype "passive"))
      (node (ref "R9") (pin "1") (pinfunction "1_1") (pintype "passive"))
    )
    (net (code "16") (name "Net-(7-PadOUT)") (class "Default")
      (node (ref "7") (pin "OUT") (pinfunction "OUT_OUT") (pintype "passive"))
      (node (ref "8") (pin "IN") (pinfunction "IN_IN") (pintype "input"))
      (node (ref "C19") (pin "2") (pinfunction "2_2") (pintype "passive"))
      (node (ref "JP4") (pin "7") (pinfunction "7_7") (pintype "passive"))
      (node (ref "JP4") (pin "8") (pinfunction "8_8") (pintype "passive"))
      (node (ref "R11") (pin "1") (pinfunction "1_1") (pintype "passive"))
    )
    (net (code "17") (name "Net-(8-PadOUT)") (class "Default")
      (node (ref "8") (pin "OUT") (pinfunction "OUT_OUT") (pintype "passive"))
      (node (ref "C21") (pin "1") (pinfunction "1_1") (pintype "passive"))
      (node (ref "JP4") (pin "5") (pinfunction "5_5") (pintype "passive"))
      (node (ref "JP4") (pin "6") (pinfunction "6_6") (pintype "passive"))
      (node (ref "R10") (pin "1") (pinfunction "1_1") (pintype "passive"))
    )
    (net (code "18") (name "Net-(9-PadOUT)") (class "Default")
      (node (ref "9") (pin "OUT") (pinfunction "OUT_OUT") (pintype "passive"))
      (node (ref "C20") (pin "2") (pinfunction "2_2") (pintype "passive"))
      (node (ref "JP4") (pin "15") (pinfunction "15_15") (pintype "passive"))
      (node (ref "JP4") (pin "16") (pinfunction "16_16") (pintype "passive"))
      (node (ref "R12") (pin "1") (pinfunction "1_1") (pintype "passive"))
    )
    (net (code "19") (name "Net-(10-PadOUT)") (class "Default")
      (node (ref "10") (pin "OUT") (pinfunction "OUT_OUT") (pintype "passive"))
      (node (ref "11") (pin "IN") (pinfunction "IN_IN") (pintype "input"))
      (node (ref "C24") (pin "2") (pinfunction "2_2") (pintype "passive"))
      (node (ref "JP5") (pin "7") (pinfunction "7_7") (pintype "passive"))
      (node (ref "JP5") (pin "8") (pinfunction "8_8") (pintype "passive"))
      (node (ref "R14") (pin "1") (pinfunction "1_1") (pintype "passive"))
    )
    (net (code "20") (name "Net-(11-PadOUT)") (class "Default")
      (node (ref "11") (pin "OUT") (pinfunction "OUT_OUT") (pintype "passive"))
      (node (ref "C26") (pin "1") (pinfunction "1_1") (pintype "passive"))
      (node (ref "JP5") (pin "5") (pinfunction "5_5") (pintype "passive"))
      (node (ref "JP5") (pin "6") (pinfunction "6_6") (pintype "passive"))
      (node (ref "R13") (pin "1") (pinfunction "1_1") (pintype "passive"))
    )
    (net (code "21") (name "Net-(12-PadOUT)") (class "Default")
      (node (ref "12") (pin "OUT") (pinfunction "OUT_OUT") (pintype "passive"))
      (node (ref "C25") (pin "2") (pinfunction "2_2") (pintype "passive"))
      (node (ref "JP5") (pin "15") (pinfunction "15_15") (pintype "passive"))
      (node (ref "JP5") (pin "16") (pinfunction "16_16") (pintype "passive"))
      (node (ref "R15") (pin "1") (pinfunction "1_1") (pintype "passive"))
    )
    (net (code "22") (name "Net-(13-PadOUT)") (class "Default")
      (node (ref "13") (pin "OUT") (pinfunction "OUT_OUT") (pintype "passive"))
      (node (ref "14") (pin "IN") (pinfunction "IN_IN") (pintype "input"))
      (node (ref "C29") (pin "2") (pinfunction "2_2") (pintype "passive"))
      (node (ref "JP6") (pin "7") (pinfunction "7_7") (pintype "passive"))
      (node (ref "JP6") (pin "8") (pinfunction "8_8") (pintype "passive"))
      (node (ref "R17") (pin "1") (pinfunction "1_1") (pintype "passive"))
    )
    (net (code "23") (name "Net-(14-PadOUT)") (class "Default")
      (node (ref "14") (pin "OUT") (pinfunction "OUT_OUT") (pintype "passive"))
      (node (ref "C31") (pin "1") (pinfunction "1_1") (pintype "passive"))
      (node (ref "JP6") (pin "5") (pinfunction "5_5") (pintype "passive"))
      (node (ref "JP6") (pin "6") (pinfunction "6_6") (pintype "passive"))
      (node (ref "R16") (pin "1") (pinfunction "1_1") (pintype "passive"))
    )
    (net (code "24") (name "Net-(15-PadOUT)") (class "Default")
      (node (ref "15") (pin "OUT") (pinfunction "OUT_OUT") (pintype "passive"))
      (node (ref "C30") (pin "2") (pinfunction "2_2") (pintype "passive"))
      (node (ref "JP6") (pin "15") (pinfunction "15_15") (pintype "passive"))
      (node (ref "JP6") (pin "16") (pinfunction "16_16") (pintype "passive"))
      (node (ref "R18") (pin "1") (pinfunction "1_1") (pintype "passive"))
    )
    (net (code "25") (name "Net-(7805-PadIN)") (class "Default")
      (node (ref "7805") (pin "IN") (pinfunction "IN_IN") (pintype "input"))
      (node (ref "7812") (pin "OUT") (pinfunction "OUT_OUT") (pintype "passive"))
      (node (ref "C1") (pin "2") (pinfunction "2_2") (pintype "passive"))
      (node (ref "JP1") (pin "7") (pinfunction "7_7") (pintype "passive"))
      (node (ref "JP1") (pin "8") (pinfunction "8_8") (pintype "passive"))
      (node (ref "R2") (pin "1") (pinfunction "1_1") (pintype "passive"))
    )
    (net (code "26") (name "Net-(7805-PadOUT)") (class "Default")
      (node (ref "7805") (pin "OUT") (pinfunction "OUT_OUT") (pintype "passive"))
      (node (ref "C15") (pin "1") (pinfunction "1_1") (pintype "passive"))
      (node (ref "JP1") (pin "5") (pinfunction "5_5") (pintype "passive"))
      (node (ref "JP1") (pin "6") (pinfunction "6_6") (pintype "passive"))
      (node (ref "R1") (pin "1") (pinfunction "1_1") (pintype "passive"))
    )
    (net (code "27") (name "Net-(7912-PadOUT)") (class "Default")
      (node (ref "7912") (pin "OUT") (pinfunction "OUT_OUT") (pintype "passive"))
      (node (ref "C2") (pin "2") (pinfunction "2_2") (pintype "passive"))
      (node (ref "JP1") (pin "15") (pinfunction "15_15") (pintype "passive"))
      (node (ref "JP1") (pin "16") (pinfunction "16_16") (pintype "passive"))
      (node (ref "R3") (pin "1") (pinfunction "1_1") (pintype "passive"))
    )
    (net (code "28") (name "Net-(C4-+)") (class "Default")
      (node (ref "7812") (pin "IN") (pinfunction "IN_IN") (pintype "input"))
      (node (ref "C4") (pin "1") (pinfunction "+_1") (pintype "passive"))
      (node (ref "D1") (pin "C") (pinfunction "C_C") (pintype "passive"))
    )
    (net (code "29") (name "Net-(C5-+)") (class "Default")
      (node (ref "7912") (pin "IN") (pinfunction "IN_IN") (pintype "input"))
      (node (ref "C5") (pin "1") (pinfunction "+_1") (pintype "passive"))
      (node (ref "D2") (pin "A") (pinfunction "A_A") (pintype "passive"))
    )
    (net (code "30") (name "Net-(C8-+)") (class "Default")
      (node (ref "1") (pin "IN") (pinfunction "IN_IN") (pintype "input"))
      (node (ref "C8") (pin "1") (pinfunction "+_1") (pintype "passive"))
      (node (ref "D3") (pin "C") (pinfunction "C_C") (pintype "passive"))
    )
    (net (code "31") (name "Net-(C9-+)") (class "Default")
      (node (ref "3") (pin "IN") (pinfunction "IN_IN") (pintype "input"))
      (node (ref "C9") (pin "1") (pinfunction "+_1") (pintype "passive"))
      (node (ref "D4") (pin "A") (pinfunction "A_A") (pintype "passive"))
    )
    (net (code "32") (name "Net-(C16-+)") (class "Default")
      (node (ref "4") (pin "IN") (pinfunction "IN_IN") (pintype "input"))
      (node (ref "C16") (pin "1") (pinfunction "+_1") (pintype "passive"))
      (node (ref "D7") (pin "C") (pinfunction "C_C") (pintype "passive"))
    )
    (net (code "33") (name "Net-(C17-+)") (class "Default")
      (node (ref "6") (pin "IN") (pinfunction "IN_IN") (pintype "input"))
      (node (ref "C17") (pin "1") (pinfunction "+_1") (pintype "passive"))
      (node (ref "D8") (pin "A") (pinfunction "A_A") (pintype "passive"))
    )
    (net (code "34") (name "Net-(C22-+)") (class "Default")
      (node (ref "7") (pin "IN") (pinfunction "IN_IN") (pintype "input"))
      (node (ref "C22") (pin "1") (pinfunction "+_1") (pintype "passive"))
      (node (ref "D9") (pin "C") (pinfunction "C_C") (pintype "passive"))
    )
    (net (code "35") (name "Net-(C23-+)") (class "Default")
      (node (ref "9") (pin "IN") (pinfunction "IN_IN") (pintype "input"))
      (node (ref "C23") (pin "1") (pinfunction "+_1") (pintype "passive"))
      (node (ref "D10") (pin "A") (pinfunction "A_A") (pintype "passive"))
    )
    (net (code "36") (name "Net-(C27-+)") (class "Default")
      (node (ref "10") (pin "IN") (pinfunction "IN_IN") (pintype "input"))
      (node (ref "C27") (pin "1") (pinfunction "+_1") (pintype "passive"))
      (node (ref "D11") (pin "C") (pinfunction "C_C") (pintype "passive"))
    )
    (net (code "37") (name "Net-(C28-+)") (class "Default")
      (node (ref "12") (pin "IN") (pinfunction "IN_IN") (pintype "input"))
      (node (ref "C28") (pin "1") (pinfunction "+_1") (pintype "passive"))
      (node (ref "D12") (pin "A") (pinfunction "A_A") (pintype "passive"))
    )
    (net (code "38") (name "Net-(C32-+)") (class "Default")
      (node (ref "13") (pin "IN") (pinfunction "IN_IN") (pintype "input"))
      (node (ref "C32") (pin "1") (pinfunction "+_1") (pintype "passive"))
      (node (ref "D13") (pin "C") (pinfunction "C_C") (pintype "passive"))
    )
    (net (code "39") (name "Net-(C33-+)") (class "Default")
      (node (ref "15") (pin "IN") (pinfunction "IN_IN") (pintype "input"))
      (node (ref "C33") (pin "1") (pinfunction "+_1") (pintype "passive"))
      (node (ref "D14") (pin "A") (pinfunction "A_A") (pintype "passive"))
    )
    (net (code "40") (name "Net-(LED1-PadA)") (class "Default")
      (node (ref "LED1") (pin "A") (pinfunction "A_A") (pintype "passive"))
      (node (ref "R1") (pin "2") (pinfunction "2_2") (pintype "passive"))
    )
    (net (code "41") (name "Net-(LED2-PadA)") (class "Default")
      (node (ref "LED2") (pin "A") (pinfunction "A_A") (pintype "passive"))
      (node (ref "R2") (pin "2") (pinfunction "2_2") (pintype "passive"))
    )
    (net (code "42") (name "Net-(LED3-C)") (class "Default")
      (node (ref "LED3") (pin "K") (pinfunction "C_K") (pintype "passive"))
      (node (ref "R3") (pin "2") (pinfunction "2_2") (pintype "passive"))
    )
    (net (code "43") (name "Net-(LED4-PadA)") (class "Default")
      (node (ref "LED4") (pin "A") (pinfunction "A_A") (pintype "passive"))
      (node (ref "R4") (pin "2") (pinfunction "2_2") (pintype "passive"))
    )
    (net (code "44") (name "Net-(LED5-PadA)") (class "Default")
      (node (ref "LED5") (pin "A") (pinfunction "A_A") (pintype "passive"))
      (node (ref "R5") (pin "2") (pinfunction "2_2") (pintype "passive"))
    )
    (net (code "45") (name "Net-(LED6-C)") (class "Default")
      (node (ref "LED6") (pin "K") (pinfunction "C_K") (pintype "passive"))
      (node (ref "R6") (pin "2") (pinfunction "2_2") (pintype "passive"))
    )
    (net (code "46") (name "Net-(LED7-PadA)") (class "Default")
      (node (ref "LED7") (pin "A") (pinfunction "A_A") (pintype "passive"))
      (node (ref "R7") (pin "2") (pinfunction "2_2") (pintype "passive"))
    )
    (net (code "47") (name "Net-(LED8-PadA)") (class "Default")
      (node (ref "LED8") (pin "A") (pinfunction "A_A") (pintype "passive"))
      (node (ref "R8") (pin "2") (pinfunction "2_2") (pintype "passive"))
    )
    (net (code "48") (name "Net-(LED9-C)") (class "Default")
      (node (ref "LED9") (pin "K") (pinfunction "C_K") (pintype "passive"))
      (node (ref "R9") (pin "2") (pinfunction "2_2") (pintype "passive"))
    )
    (net (code "49") (name "Net-(LED10-PadA)") (class "Default")
      (node (ref "LED10") (pin "A") (pinfunction "A_A") (pintype "passive"))
      (node (ref "R10") (pin "2") (pinfunction "2_2") (pintype "passive"))
    )
    (net (code "50") (name "Net-(LED11-PadA)") (class "Default")
      (node (ref "LED11") (pin "A") (pinfunction "A_A") (pintype "passive"))
      (node (ref "R11") (pin "2") (pinfunction "2_2") (pintype "passive"))
    )
    (net (code "51") (name "Net-(LED12-C)") (class "Default")
      (node (ref "LED12") (pin "K") (pinfunction "C_K") (pintype "passive"))
      (node (ref "R12") (pin "2") (pinfunction "2_2") (pintype "passive"))
    )
    (net (code "52") (name "Net-(LED13-PadA)") (class "Default")
      (node (ref "LED13") (pin "A") (pinfunction "A_A") (pintype "passive"))
      (node (ref "R13") (pin "2") (pinfunction "2_2") (pintype "passive"))
    )
    (net (code "53") (name "Net-(LED14-PadA)") (class "Default")
      (node (ref "LED14") (pin "A") (pinfunction "A_A") (pintype "passive"))
      (node (ref "R14") (pin "2") (pinfunction "2_2") (pintype "passive"))
    )
    (net (code "54") (name "Net-(LED15-C)") (class "Default")
      (node (ref "LED15") (pin "K") (pinfunction "C_K") (pintype "passive"))
      (node (ref "R15") (pin "2") (pinfunction "2_2") (pintype "passive"))
    )
    (net (code "55") (name "Net-(LED16-PadA)") (class "Default")
      (node (ref "LED16") (pin "A") (pinfunction "A_A") (pintype "passive"))
      (node (ref "R16") (pin "2") (pinfunction "2_2") (pintype "passive"))
    )
    (net (code "56") (name "Net-(LED17-PadA)") (class "Default")
      (node (ref "LED17") (pin "A") (pinfunction "A_A") (pintype "passive"))
      (node (ref "R17") (pin "2") (pinfunction "2_2") (pintype "passive"))
    )
    (net (code "57") (name "Net-(LED18-C)") (class "Default")
      (node (ref "LED18") (pin "K") (pinfunction "C_K") (pintype "passive"))
      (node (ref "R18") (pin "2") (pinfunction "2_2") (pintype "passive"))
    )
  )
)
